# AUDIO.net
KiCad netlist of a schematic drawn in Altium Designer
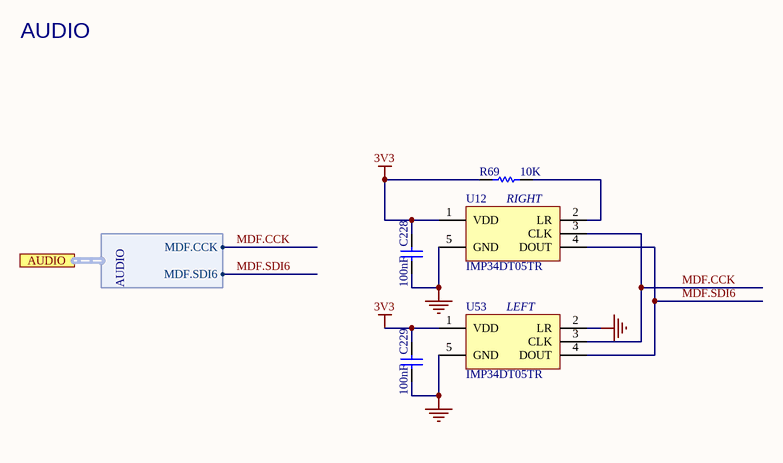
[diagram p0: AUDIO.SchDoc]

(export (version "E")
  (design (tool "Eeschema 10.0.6"))
  (components
    (comp (ref "C228")
      (value "100nF")
      (footprint "C0402")
      (description "Capacitor,100nF,16V,X7R,10%,0402")
      (fields
        (field (name "INTERNAL_PART_NUMBER") "MCD-00006")
        (field (name "MANUFACTURER_PART_NUMBER") "CC0402KRX7R7BB104")
        (field (name "PROVIDED_BY") "SUBCO")
      )
      (libsource (lib "MCD_PARTS_database") (part "Capacitor"))
    )
    (comp (ref "C229")
      (value "100nF")
      (footprint "C0402")
      (description "Capacitor,100nF,16V,X7R,10%,0402")
      (fields
        (field (name "INTERNAL_PART_NUMBER") "MCD-00006")
        (field (name "MANUFACTURER_PART_NUMBER") "CC0402KRX7R7BB104")
        (field (name "PROVIDED_BY") "SUBCO")
      )
      (libsource (lib "MCD_PARTS_database") (part "Capacitor"))
    )
    (comp (ref "R69")
      (value "10K")
      (footprint "R0402")
      (description "Resistor,10K,0402,1%,1/16W")
      (fields (field (name "INTERNAL_PART_NUMBER") "MCD-00053") (field (name "BMS_PART_NUMBER") "9131590"))
      (libsource (lib "MCD_PARTS_database") (part "Resistor"))
    )
    (comp (ref "U12")
      (value "IMP34DT05TR")
      (footprint "MIC_HCLGA_3X4X1_4LD")
      (description "MEMS audio sensor omnidirectional digital microphone for industrial applications")
      (fields (field (name "INTERNAL_PART_NUMBER") "MCD-01715") (field (name "BMS_PART_NUMBER") "9177995"))
      (libsource (lib "MCD_PARTS_database") (part "IMP34DT05TR"))
    )
    (comp (ref "U53")
      (value "IMP34DT05TR")
      (footprint "MIC_HCLGA_3X4X1_4LD")
      (description "MEMS audio sensor omnidirectional digital microphone for industrial applications")
      (fields (field (name "INTERNAL_PART_NUMBER") "MCD-01715") (field (name "BMS_PART_NUMBER") "9177995"))
      (libsource (lib "MCD_PARTS_database") (part "IMP34DT05TR"))
    )
  )
  (nets
    (net (code "2") (name "/MDF.CCK") (class "Default")
      (node (ref "U12") (pin "3") (pinfunction "CLK_3") (pintype "passive"))
      (node (ref "U53") (pin "3") (pinfunction "CLK_3") (pintype "passive"))
    )
    (net (code "3") (name "/MDF.SDI6") (class "Default")
      (node (ref "U12") (pin "4") (pinfunction "DOUT_4") (pintype "passive"))
      (node (ref "U53") (pin "4") (pinfunction "DOUT_4") (pintype "passive"))
    )
    (net (code "5") (name "3V3") (class "Default")
      (node (ref "C228") (pin "1") (pinfunction "1_1") (pintype "passive"))
      (node (ref "C229") (pin "1") (pinfunction "1_1") (pintype "passive"))
      (node (ref "R69") (pin "1") (pinfunction "1_1") (pintype "passive"))
      (node (ref "U12") (pin "1") (pinfunction "VDD_1") (pintype "passive"))
      (node (ref "U53") (pin "1") (pinfunction "VDD_1") (pintype "passive"))
    )
    (net (code "6") (name "GND") (class "Default")
      (node (ref "C228") (pin "2") (pinfunction "2_2") (pintype "passive"))
      (node (ref "C229") (pin "2") (pinfunction "2_2") (pintype "passive"))
      (node (ref "U12") (pin "5") (pinfunction "GND_5") (pintype "passive"))
      (node (ref "U53") (pin "2") (pinfunction "LR_2") (pintype "passive"))
      (node (ref "U53") (pin "5") (pinfunction "GND_5") (pintype "passive"))
    )
    (net (code "7") (name "Net-(U12-LR)") (class "Default")
      (node (ref "R69") (pin "2") (pinfunction "2_2") (pintype "passive"))
      (node (ref "U12") (pin "2") (pinfunction "LR_2") (pintype "passive"))
    )
  )
)
